# BOC_Audio.net
KiCad netlist of a schematic drawn in Altium Designer
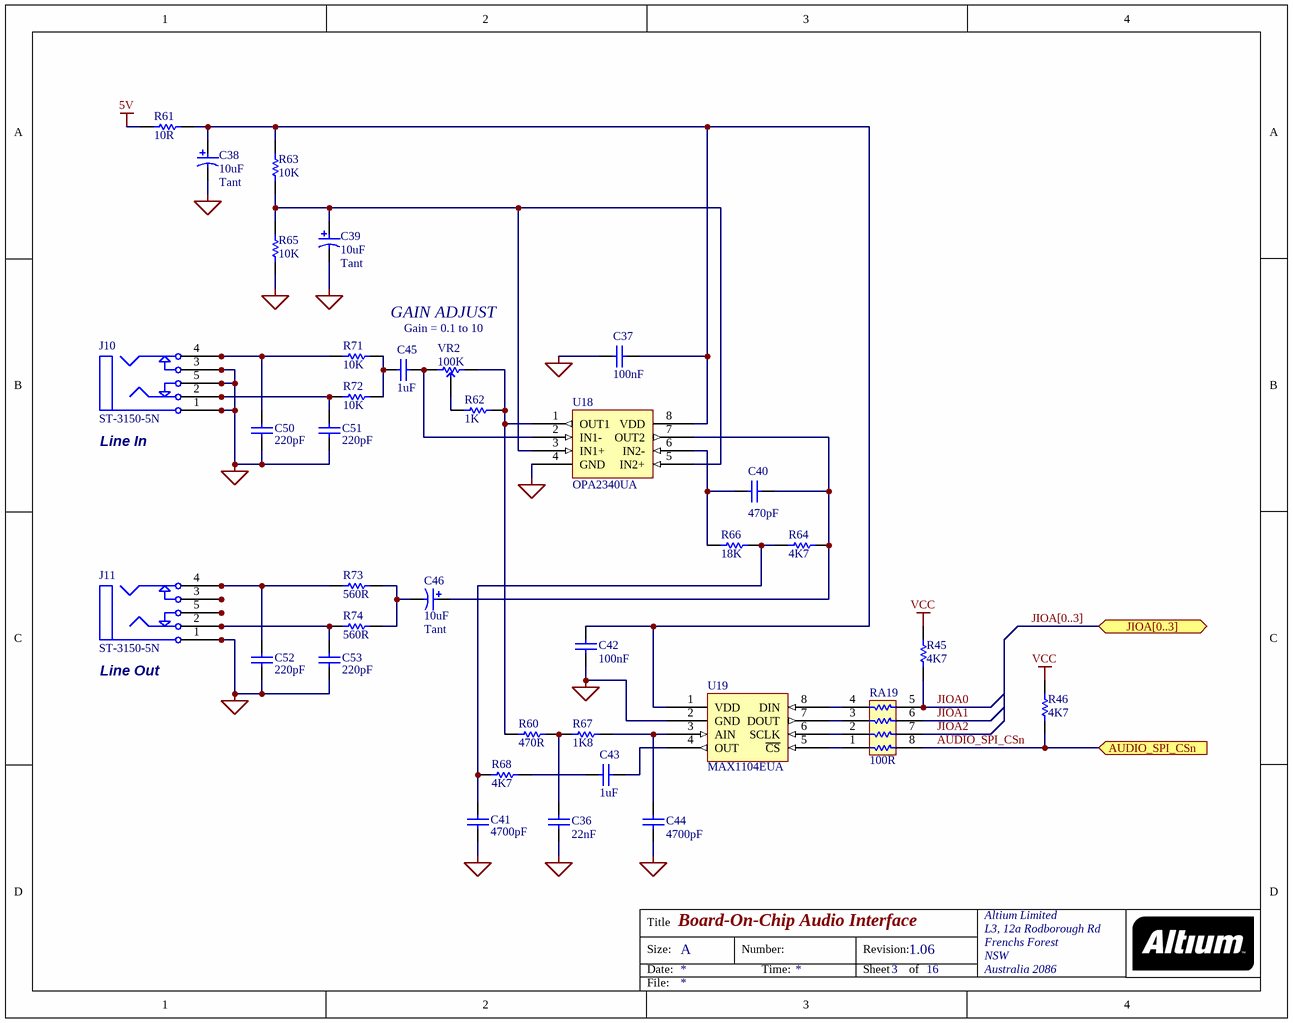
[diagram p0: BOC_Audio.SchDoc]

(export (version "E")
  (design (tool "Eeschema 10.0.6"))
  (components
    (comp (ref "C36")
      (value "22nF")
      (footprint "Altium Nanoboard Project:CC2012-0805")
      (description "Capacitor")
      (libsource (lib "Altium Nanoboard Project") (part "CAP"))
    )
    (comp (ref "C37")
      (value "100nF")
      (footprint "Altium Nanoboard Project:CC2012-0805")
      (description "Capacitor")
      (libsource (lib "Altium Nanoboard Project") (part "CAP"))
    )
    (comp (ref "C38")
      (value "10uF")
      (footprint "Altium Nanoboard Project:MCCT-B")
      (description "Polar Capacitor")
      (fields (field (name "CAPACITOR TYPE") "Tant"))
      (libsource (lib "Altium Nanoboard Project") (part "CAP_POLAR"))
    )
    (comp (ref "C39")
      (value "10uF")
      (footprint "Altium Nanoboard Project:MCCT-B")
      (description "Polar Capacitor")
      (fields (field (name "CAPACITOR TYPE") "Tant"))
      (libsource (lib "Altium Nanoboard Project") (part "CAP_POLAR"))
    )
    (comp (ref "C40")
      (value "470pF")
      (footprint "Altium Nanoboard Project:CC2012-0805")
      (description "Capacitor")
      (libsource (lib "Altium Nanoboard Project") (part "CAP"))
    )
    (comp (ref "C41")
      (value "4700pF")
      (footprint "Altium Nanoboard Project:CC2012-0805")
      (description "Capacitor")
      (libsource (lib "Altium Nanoboard Project") (part "CAP"))
    )
    (comp (ref "C42")
      (value "100nF")
      (footprint "Altium Nanoboard Project:CC2012-0805")
      (description "Capacitor")
      (libsource (lib "Altium Nanoboard Project") (part "CAP"))
    )
    (comp (ref "C43")
      (value "1uF")
      (footprint "Altium Nanoboard Project:C3216-1206")
      (description "Capacitor")
      (libsource (lib "Altium Nanoboard Project") (part "CAP"))
    )
    (comp (ref "C44")
      (value "4700pF")
      (footprint "Altium Nanoboard Project:CC2012-0805")
      (description "Capacitor")
      (libsource (lib "Altium Nanoboard Project") (part "CAP"))
    )
    (comp (ref "C45")
      (value "1uF")
      (footprint "Altium Nanoboard Project:C3216-1206")
      (description "Capacitor")
      (libsource (lib "Altium Nanoboard Project") (part "CAP"))
    )
    (comp (ref "C46")
      (value "10uF")
      (footprint "Altium Nanoboard Project:MCCT-B")
      (description "Polar Capacitor")
      (fields (field (name "CAPACITOR TYPE") "Tant"))
      (libsource (lib "Altium Nanoboard Project") (part "CAP_POLAR"))
    )
    (comp (ref "C50")
      (value "220pF")
      (footprint "Altium Nanoboard Project:CC2012-0805")
      (description "Capacitor")
      (libsource (lib "Altium Nanoboard Project") (part "CAP"))
    )
    (comp (ref "C51")
      (value "220pF")
      (footprint "Altium Nanoboard Project:CC2012-0805")
      (description "Capacitor")
      (libsource (lib "Altium Nanoboard Project") (part "CAP"))
    )
    (comp (ref "C52")
      (value "220pF")
      (footprint "Altium Nanoboard Project:CC2012-0805")
      (description "Capacitor")
      (libsource (lib "Altium Nanoboard Project") (part "CAP"))
    )
    (comp (ref "C53")
      (value "220pF")
      (footprint "Altium Nanoboard Project:CC2012-0805")
      (description "Capacitor")
      (libsource (lib "Altium Nanoboard Project") (part "CAP"))
    )
    (comp (ref "J10")
      (value "ST-3150-5N")
      (footprint "Altium Nanoboard Project:ST-3150-5N")
      (description "3-Conductor Jack with 2 break contacts (normals) and 2 auxiliary make contacts")
      (fields (field (name "MANUFACTURER") "Kycon") (field (name "PUBLISHER") "Altium Limited"))
      (libsource (lib "Altium Nanoboard Project") (part "ST-3150-5N"))
    )
    (comp (ref "J11")
      (value "ST-3150-5N")
      (footprint "Altium Nanoboard Project:ST-3150-5N")
      (description "3-Conductor Jack with 2 break contacts (normals) and 2 auxiliary make contacts")
      (fields (field (name "MANUFACTURER") "Kycon") (field (name "PUBLISHER") "Altium Limited"))
      (libsource (lib "Altium Nanoboard Project") (part "ST-3150-5N"))
    )
    (comp (ref "R45")
      (value "4K7")
      (footprint "Altium Nanoboard Project:CC2012-0805")
      (description "Resistor")
      (libsource (lib "Altium Nanoboard Project") (part "RES"))
    )
    (comp (ref "R46")
      (value "4K7")
      (footprint "Altium Nanoboard Project:CC2012-0805")
      (description "Resistor")
      (libsource (lib "Altium Nanoboard Project") (part "RES"))
    )
    (comp (ref "R60")
      (value "470R")
      (footprint "Altium Nanoboard Project:CC2012-0805")
      (description "Resistor")
      (libsource (lib "Altium Nanoboard Project") (part "RES"))
    )
    (comp (ref "R61")
      (value "10R")
      (footprint "Altium Nanoboard Project:CC2012-0805")
      (description "Resistor")
      (libsource (lib "Altium Nanoboard Project") (part "RES"))
    )
    (comp (ref "R62")
      (value "1K")
      (footprint "Altium Nanoboard Project:CC2012-0805")
      (description "Resistor")
      (libsource (lib "Altium Nanoboard Project") (part "RES"))
    )
    (comp (ref "R63")
      (value "10K")
      (footprint "Altium Nanoboard Project:CC2012-0805")
      (description "Resistor")
      (libsource (lib "Altium Nanoboard Project") (part "RES"))
    )
    (comp (ref "R64")
      (value "4K7")
      (footprint "Altium Nanoboard Project:CC2012-0805")
      (description "Resistor")
      (libsource (lib "Altium Nanoboard Project") (part "RES"))
    )
    (comp (ref "R65")
      (value "10K")
      (footprint "Altium Nanoboard Project:CC2012-0805")
      (description "Resistor")
      (libsource (lib "Altium Nanoboard Project") (part "RES"))
    )
    (comp (ref "R66")
      (value "18K")
      (footprint "Altium Nanoboard Project:CC2012-0805")
      (description "Resistor")
      (libsource (lib "Altium Nanoboard Project") (part "RES"))
    )
    (comp (ref "R67")
      (value "1K8")
      (footprint "Altium Nanoboard Project:CC2012-0805")
      (description "Resistor")
      (libsource (lib "Altium Nanoboard Project") (part "RES"))
    )
    (comp (ref "R68")
      (value "4K7")
      (footprint "Altium Nanoboard Project:CC2012-0805")
      (description "Resistor")
      (libsource (lib "Altium Nanoboard Project") (part "RES"))
    )
    (comp (ref "R71")
      (value "10K")
      (footprint "Altium Nanoboard Project:CC2012-0805")
      (description "Resistor")
      (libsource (lib "Altium Nanoboard Project") (part "RES"))
    )
    (comp (ref "R72")
      (value "10K")
      (footprint "Altium Nanoboard Project:CC2012-0805")
      (description "Resistor")
      (libsource (lib "Altium Nanoboard Project") (part "RES"))
    )
    (comp (ref "R73")
      (value "560R")
      (footprint "Altium Nanoboard Project:CC2012-0805")
      (description "Resistor")
      (libsource (lib "Altium Nanoboard Project") (part "RES"))
    )
    (comp (ref "R74")
      (value "560R")
      (footprint "Altium Nanoboard Project:CC2012-0805")
      (description "Resistor")
      (libsource (lib "Altium Nanoboard Project") (part "RES"))
    )
    (comp (ref "RA19")
      (value "100R")
      (footprint "Altium Nanoboard Project:MNR34")
      (description "3216x4 Resistor Array")
      (libsource (lib "Altium Nanoboard Project") (part "MNR34"))
    )
    (comp (ref "U18")
      (value "OPA2340UA")
      (footprint "Altium Nanoboard Project:SO-G8")
      (fields (field (name "MANUFACTURER") "Burr-Brown"))
      (libsource (lib "Altium Nanoboard Project") (part "OPA2340UA"))
    )
    (comp (ref "U19")
      (value "MAX1104EUA")
      (footprint "Altium Nanoboard Project:TSSO3X5-G8/X.35")
      (description "8 bit CODEC with 4 wire logic interface")
      (fields (field (name "MANUFACTURER") "Maxim"))
      (libsource (lib "Altium Nanoboard Project") (part "MAX1104EUA"))
    )
    (comp (ref "VR2")
      (value "100K")
      (footprint "Altium Nanoboard Project:POT4MM-2")
      (description "Potentiometer")
      (libsource (lib "Altium Nanoboard Project") (part "POT_M"))
    )
  )
  (nets
    (net (code "2") (name "/AUDIO_SPI_CSn") (class "Default")
      (node (ref "R46") (pin "1") (pinfunction "1_1") (pintype "passive"))
      (node (ref "RA19") (pin "8") (pintype "passive"))
    )
    (net (code "3") (name "/JIOA0") (class "Default")
      (node (ref "R45") (pin "1") (pinfunction "1_1") (pintype "passive"))
      (node (ref "RA19") (pin "5") (pintype "passive"))
    )
    (net (code "4") (name "/JIOA1") (class "Default") (node (ref "RA19") (pin "6") (pintype "passive")))
    (net (code "5") (name "/JIOA2") (class "Default") (node (ref "RA19") (pin "7") (pintype "passive")))
    (net (code "7") (name "5V") (class "Default")
      (node (ref "R61") (pin "1") (pinfunction "1_1") (pintype "passive"))
    )
    (net (code "8") (name "AGND") (class "Default")
      (node (ref "C36") (pin "2") (pinfunction "2_2") (pintype "passive"))
      (node (ref "C37") (pin "1") (pinfunction "1_1") (pintype "passive"))
      (node (ref "C38") (pin "2") (pinfunction "2_2") (pintype "passive"))
      (node (ref "C39") (pin "2") (pinfunction "2_2") (pintype "passive"))
      (node (ref "C41") (pin "2") (pinfunction "2_2") (pintype "passive"))
      (node (ref "C42") (pin "2") (pinfunction "2_2") (pintype "passive"))
      (node (ref "C44") (pin "2") (pinfunction "2_2") (pintype "passive"))
      (node (ref "C50") (pin "2") (pinfunction "2_2") (pintype "passive"))
      (node (ref "C51") (pin "2") (pinfunction "2_2") (pintype "passive"))
      (node (ref "C52") (pin "2") (pinfunction "2_2") (pintype "passive"))
      (node (ref "C53") (pin "2") (pinfunction "2_2") (pintype "passive"))
      (node (ref "J10") (pin "1") (pintype "passive"))
      (node (ref "J10") (pin "1A") (pintype "passive"))
      (node (ref "J10") (pin "1B") (pintype "passive"))
      (node (ref "J10") (pin "3") (pintype "passive"))
      (node (ref "J10") (pin "3A") (pintype "passive"))
      (node (ref "J10") (pin "3B") (pintype "passive"))
      (node (ref "J10") (pin "5") (pintype "passive"))
      (node (ref "J10") (pin "5A") (pintype "passive"))
      (node (ref "J10") (pin "5B") (pintype "passive"))
      (node (ref "J11") (pin "1") (pintype "passive"))
      (node (ref "J11") (pin "1A") (pintype "passive"))
      (node (ref "J11") (pin "1B") (pintype "passive"))
      (node (ref "R65") (pin "1") (pinfunction "1_1") (pintype "passive"))
      (node (ref "U18") (pin "4") (pinfunction "GND_4") (pintype "power_in"))
      (node (ref "U19") (pin "2") (pinfunction "GND_2") (pintype "power_in"))
    )
    (net (code "9") (name "Net-(C36-Pad1)") (class "Default")
      (node (ref "C36") (pin "1") (pinfunction "1_1") (pintype "passive"))
      (node (ref "R60") (pin "2") (pinfunction "2_2") (pintype "passive"))
      (node (ref "R67") (pin "1") (pinfunction "1_1") (pintype "passive"))
    )
    (net (code "10") (name "Net-(C41-Pad1)") (class "Default")
      (node (ref "C41") (pin "1") (pinfunction "1_1") (pintype "passive"))
      (node (ref "R64") (pin "2") (pinfunction "2_2") (pintype "passive"))
      (node (ref "R66") (pin "1") (pinfunction "1_1") (pintype "passive"))
      (node (ref "R68") (pin "1") (pinfunction "1_1") (pintype "passive"))
    )
    (net (code "11") (name "Net-(C43-Pad1)") (class "Default")
      (node (ref "C43") (pin "1") (pinfunction "1_1") (pintype "passive"))
      (node (ref "R68") (pin "2") (pinfunction "2_2") (pintype "passive"))
    )
    (net (code "12") (name "Net-(C45-Pad1)") (class "Default")
      (node (ref "C45") (pin "1") (pinfunction "1_1") (pintype "passive"))
      (node (ref "R71") (pin "2") (pinfunction "2_2") (pintype "passive"))
      (node (ref "R72") (pin "2") (pinfunction "2_2") (pintype "passive"))
    )
    (net (code "13") (name "Net-(C46-Pad2)") (class "Default")
      (node (ref "C46") (pin "2") (pinfunction "2_2") (pintype "passive"))
      (node (ref "R73") (pin "2") (pinfunction "2_2") (pintype "passive"))
      (node (ref "R74") (pin "2") (pinfunction "2_2") (pintype "passive"))
    )
    (net (code "14") (name "Net-(C50-Pad1)") (class "Default")
      (node (ref "C50") (pin "1") (pinfunction "1_1") (pintype "passive"))
      (node (ref "J10") (pin "4") (pintype "passive"))
      (node (ref "J10") (pin "4A") (pintype "passive"))
      (node (ref "J10") (pin "4B") (pintype "passive"))
      (node (ref "R71") (pin "1") (pinfunction "1_1") (pintype "passive"))
    )
    (net (code "15") (name "Net-(C51-Pad1)") (class "Default")
      (node (ref "C51") (pin "1") (pinfunction "1_1") (pintype "passive"))
      (node (ref "J10") (pin "2") (pintype "passive"))
      (node (ref "J10") (pin "2A") (pintype "passive"))
      (node (ref "J10") (pin "2B") (pintype "passive"))
      (node (ref "R72") (pin "1") (pinfunction "1_1") (pintype "passive"))
    )
    (net (code "16") (name "Net-(C52-Pad1)") (class "Default")
      (node (ref "C52") (pin "1") (pinfunction "1_1") (pintype "passive"))
      (node (ref "J11") (pin "4") (pintype "passive"))
      (node (ref "J11") (pin "4A") (pintype "passive"))
      (node (ref "J11") (pin "4B") (pintype "passive"))
      (node (ref "R73") (pin "1") (pinfunction "1_1") (pintype "passive"))
    )
    (net (code "17") (name "Net-(C53-Pad1)") (class "Default")
      (node (ref "C53") (pin "1") (pinfunction "1_1") (pintype "passive"))
      (node (ref "J11") (pin "2") (pintype "passive"))
      (node (ref "J11") (pin "2A") (pintype "passive"))
      (node (ref "J11") (pin "2B") (pintype "passive"))
      (node (ref "R74") (pin "1") (pinfunction "1_1") (pintype "passive"))
    )
    (net (code "18") (name "Net-(J11-Pad3)") (class "Default")
      (node (ref "J11") (pin "3") (pintype "passive"))
      (node (ref "J11") (pin "3A") (pintype "passive"))
      (node (ref "J11") (pin "3B") (pintype "passive"))
    )
    (net (code "19") (name "Net-(J11-Pad5)") (class "Default")
      (node (ref "J11") (pin "5") (pintype "passive"))
      (node (ref "J11") (pin "5A") (pintype "passive"))
      (node (ref "J11") (pin "5B") (pintype "passive"))
    )
    (net (code "20") (name "Net-(R62-Pad1)") (class "Default")
      (node (ref "R62") (pin "1") (pinfunction "1_1") (pintype "passive"))
      (node (ref "VR2") (pin "W") (pintype "passive"))
    )
    (net (code "21") (name "Net-(U18-IN1+)") (class "Default")
      (node (ref "C39") (pin "1") (pinfunction "1_1") (pintype "passive"))
      (node (ref "R63") (pin "1") (pinfunction "1_1") (pintype "passive"))
      (node (ref "R65") (pin "2") (pinfunction "2_2") (pintype "passive"))
      (node (ref "U18") (pin "3") (pinfunction "IN1+_3") (pintype "input"))
      (node (ref "U18") (pin "5") (pinfunction "IN2+_5") (pintype "input"))
    )
    (net (code "22") (name "Net-(U18-IN1-)") (class "Default")
      (node (ref "C45") (pin "2") (pinfunction "2_2") (pintype "passive"))
      (node (ref "U18") (pin "2") (pinfunction "IN1-_2") (pintype "input"))
      (node (ref "VR2") (pin "CCW") (pinfunction "-_CCW") (pintype "passive"))
    )
    (net (code "23") (name "Net-(U18-IN2-)") (class "Default")
      (node (ref "C40") (pin "1") (pinfunction "1_1") (pintype "passive"))
      (node (ref "R66") (pin "2") (pinfunction "2_2") (pintype "passive"))
      (node (ref "U18") (pin "6") (pinfunction "IN2-_6") (pintype "input"))
    )
    (net (code "24") (name "Net-(U18-OUT1)") (class "Default")
      (node (ref "R60") (pin "1") (pinfunction "1_1") (pintype "passive"))
      (node (ref "R62") (pin "2") (pinfunction "2_2") (pintype "passive"))
      (node (ref "U18") (pin "1") (pinfunction "OUT1_1") (pintype "output"))
      (node (ref "VR2") (pin "CW") (pinfunction "+_CW") (pintype "passive"))
    )
    (net (code "25") (name "Net-(U18-OUT2)") (class "Default")
      (node (ref "C40") (pin "2") (pinfunction "2_2") (pintype "passive"))
      (node (ref "C46") (pin "1") (pinfunction "1_1") (pintype "passive"))
      (node (ref "R64") (pin "1") (pinfunction "1_1") (pintype "passive"))
      (node (ref "U18") (pin "7") (pinfunction "OUT2_7") (pintype "output"))
    )
    (net (code "26") (name "Net-(U18-VDD)") (class "Default")
      (node (ref "C37") (pin "2") (pinfunction "2_2") (pintype "passive"))
      (node (ref "C38") (pin "1") (pinfunction "1_1") (pintype "passive"))
      (node (ref "C42") (pin "1") (pinfunction "1_1") (pintype "passive"))
      (node (ref "R61") (pin "2") (pinfunction "2_2") (pintype "passive"))
      (node (ref "R63") (pin "2") (pinfunction "2_2") (pintype "passive"))
      (node (ref "U18") (pin "8") (pinfunction "VDD_8") (pintype "power_in"))
      (node (ref "U19") (pin "1") (pinfunction "VDD_1") (pintype "power_in"))
    )
    (net (code "27") (name "Net-(U19-AIN)") (class "Default")
      (node (ref "C44") (pin "1") (pinfunction "1_1") (pintype "passive"))
      (node (ref "R67") (pin "2") (pinfunction "2_2") (pintype "passive"))
      (node (ref "U19") (pin "3") (pinfunction "AIN_3") (pintype "input"))
    )
    (net (code "28") (name "Net-(U19-DIN)") (class "Default")
      (node (ref "RA19") (pin "4") (pintype "passive"))
      (node (ref "U19") (pin "8") (pinfunction "DIN_8") (pintype "input"))
    )
    (net (code "29") (name "Net-(U19-DOUT)") (class "Default")
      (node (ref "RA19") (pin "3") (pintype "passive"))
      (node (ref "U19") (pin "7") (pinfunction "DOUT_7") (pintype "output"))
    )
    (net (code "30") (name "Net-(U19-OUT)") (class "Default")
      (node (ref "C43") (pin "2") (pinfunction "2_2") (pintype "passive"))
      (node (ref "U19") (pin "4") (pinfunction "OUT_4") (pintype "output"))
    )
    (net (code "31") (name "Net-(U19-SCLK)") (class "Default")
      (node (ref "RA19") (pin "2") (pintype "passive"))
      (node (ref "U19") (pin "6") (pinfunction "SCLK_6") (pintype "input"))
    )
    (net (code "32") (name "Net-(U19-~{CS})") (class "Default")
      (node (ref "RA19") (pin "1") (pintype "passive"))
      (node (ref "U19") (pin "5") (pinfunction "~{CS}_5") (pintype "input"))
    )
    (net (code "33") (name "VCC") (class "Default")
      (node (ref "R45") (pin "2") (pinfunction "2_2") (pintype "passive"))
      (node (ref "R46") (pin "2") (pinfunction "2_2") (pintype "passive"))
    )
  )
)
